# Air_quality.net
KiCad netlist of a schematic drawn in Altium Designer
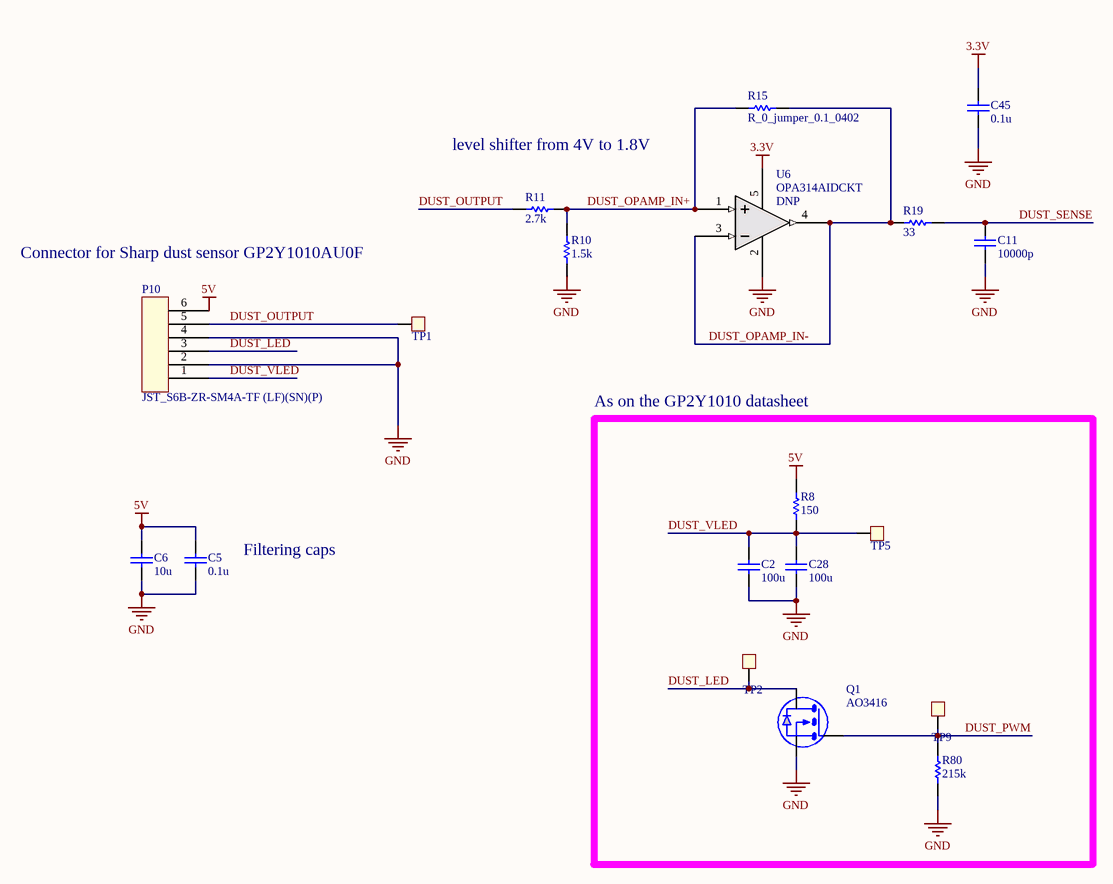
[diagram p0: Air_quality.SchDoc]

(export (version "E")
  (design (tool "Eeschema 10.0.6"))
  (components
    (comp (ref "C2")
      (value "100u")
      (footprint "CAP1206_SENSE_DVT")
      (description "Chip capacitor")
      (fields (field (name "TOLERANCE") "20%") (field (name "VOLTAGE") "10V"))
      (libsource (lib "Morpheus_pill") (part "C_100u_20_10_X5R_1206"))
    )
    (comp (ref "C5")
      (value "0.1u")
      (footprint "CAP0603_SENSE_DVT")
      (description "Chip capacitor")
      (fields (field (name "TOLERANCE") "20%") (field (name "VOLTAGE") "16V"))
      (libsource (lib "Morpheus_pill") (part "C_0.1u_20_16_X7R_0603"))
    )
    (comp (ref "C6")
      (value "10u")
      (footprint "CAP0603_SENSE_DVT")
      (description "Chip capacitor")
      (fields (field (name "TOLERANCE") "10%") (field (name "VOLTAGE") "6.3V"))
      (libsource (lib "Morpheus_pill") (part "C_10u_10_6.3_X5R_0603"))
    )
    (comp (ref "C11")
      (value "10000p")
      (footprint "CAP0402_SENSE_DVT")
      (description "Chip capacitor")
      (fields (field (name "TOLERANCE") "10%") (field (name "VOLTAGE") "50V"))
      (libsource (lib "Morpheus_pill") (part "C_10000p_10_50_X7R_0402"))
    )
    (comp (ref "C28")
      (value "100u")
      (footprint "CAP1206_SENSE_DVT")
      (description "Chip capacitor")
      (fields (field (name "TOLERANCE") "20%") (field (name "VOLTAGE") "10V"))
      (libsource (lib "Morpheus_pill") (part "C_100u_20_10_X5R_1206"))
    )
    (comp (ref "C45")
      (value "0.1u")
      (footprint "CAP0402_SENSE_DVT")
      (description "Chip capacitor")
      (fields (field (name "TOLERANCE") "10%") (field (name "VOLTAGE") "50V"))
      (libsource (lib "Morpheus_pill") (part "C_0.1u_10_50_X7R_0402"))
    )
    (comp (ref "P10")
      (value "JST_S6B-ZR-SM4A-TF (LF)(SN)(P)")
      (footprint "JST_S6B-ZR-SM4A-TF (LF)(SN)(P)")
      (description "6-pin JST connector")
      (libsource (lib "Morpheus_pill") (part "JST_S6B-ZR-SM4A-TF (LF)(SN)(P)"))
    )
    (comp (ref "Q1")
      (value "AO3416")
      (footprint "SOT-23")
      (description "N-channel enhancement mode FET")
      (libsource (lib "Morpheus_pill") (part "AO3416"))
    )
    (comp (ref "R8")
      (value "150")
      (footprint "RES0805_SENSE_DVT")
      (description "Chip Resistor")
      (fields (field (name "TOLERANCE") "5 %") (field (name "POWER") "0.125 W"))
      (libsource (lib "Morpheus_pill") (part "R_150_5_0.125_0805"))
    )
    (comp (ref "R10")
      (value "1.5k")
      (footprint "RES0603_SENSE_DVT")
      (description "Chip Resistor")
      (fields (field (name "TOLERANCE") "1 %") (field (name "POWER") "0.1 W"))
      (libsource (lib "Morpheus_pill") (part "R_1.5k_1_0.1_0603"))
    )
    (comp (ref "R11")
      (value "2.7k")
      (footprint "RES0402_SENSE_DVT")
      (description "RES SMD 2.7K OHM 1% 1/16W 0402")
      (fields (field (name "TOLERANCE") "1 %") (field (name "POWER") "1/16W"))
      (libsource (lib "Morpheus_pill") (part "R_2.7k_1_0.1_0402"))
    )
    (comp (ref "R15")
      (value "R_0_jumper_0.1_0402")
      (footprint "RES0402-SENSE-DVT")
      (description "Chip Resistor")
      (fields (field (name "TOLERANCE") "Jumper") (field (name "POWER") "0.1 W"))
      (libsource (lib "Morpheus_pill") (part "R_0_jumper_0.1_0402"))
    )
    (comp (ref "R19")
      (value "33")
      (footprint "RES0402_SENSE_DVT")
      (description "Chip Resistor")
      (fields (field (name "TOLERANCE") "5 %") (field (name "POWER") "0.1 W"))
      (libsource (lib "Morpheus_pill") (part "R_33_5_0.1_0402"))
    )
    (comp (ref "R80")
      (value "215k")
      (footprint "RES0402_SENSE_DVT")
      (description "Chip Resistor")
      (fields (field (name "TOLERANCE") "1 %") (field (name "POWER") "0.1 W"))
      (libsource (lib "Morpheus_pill") (part "R_215K_1_0.1_0402"))
    )
    (comp (ref "TP1")
      (value "TP")
      (footprint "TP-1.1")
      (description "testpoint")
      (libsource (lib "Morpheus_pill") (part "TP"))
    )
    (comp (ref "TP2")
      (value "TP")
      (footprint "TP-1.1")
      (description "testpoint")
      (libsource (lib "") (part "TP_1"))
    )
    (comp (ref "TP5")
      (value "TP")
      (footprint "TP-1.1")
      (description "testpoint")
      (libsource (lib "Morpheus_pill") (part "TP"))
    )
    (comp (ref "TP9")
      (value "TP")
      (footprint "TP-1.1")
      (description "testpoint")
      (libsource (lib "") (part "TP_1"))
    )
    (comp (ref "U6")
      (value "DNP")
      (footprint "SC-70-5")
      (description "TI single 1.8-5.5V OPAMP")
      (fields (field (name "PN") "OPA314AIDCKT"))
      (libsource (lib "Morpheus_pill") (part "OPA314AIDCKT"))
    )
  )
  (nets
    (net (code "1") (name "/DUST_LED") (class "Default")
      (node (ref "P10") (pin "3") (pintype "passive"))
      (node (ref "Q1") (pin "3") (pinfunction "D_3") (pintype "passive"))
      (node (ref "TP2") (pin "1") (pinfunction "1_1") (pintype "passive"))
    )
    (net (code "2") (name "/DUST_OPAMP_IN+") (class "Default")
      (node (ref "R10") (pin "1") (pinfunction "1_1") (pintype "passive"))
      (node (ref "R11") (pin "2") (pinfunction "2_2") (pintype "passive"))
      (node (ref "R15") (pin "1") (pinfunction "1_1") (pintype "passive"))
      (node (ref "U6") (pin "1") (pinfunction "IN+_1") (pintype "input"))
    )
    (net (code "3") (name "/DUST_OPAMP_IN-") (class "Default")
      (node (ref "R15") (pin "2") (pinfunction "2_2") (pintype "passive"))
      (node (ref "R19") (pin "1") (pinfunction "1_1") (pintype "passive"))
      (node (ref "U6") (pin "3") (pinfunction "IN-_3") (pintype "input"))
      (node (ref "U6") (pin "4") (pinfunction "OUT_4") (pintype "output"))
    )
    (net (code "4") (name "/DUST_OUTPUT") (class "Default")
      (node (ref "P10") (pin "5") (pintype "passive"))
      (node (ref "R11") (pin "1") (pinfunction "1_1") (pintype "passive"))
      (node (ref "TP1") (pin "1") (pinfunction "1_1") (pintype "passive"))
    )
    (net (code "5") (name "/DUST_PWM") (class "Default")
      (node (ref "Q1") (pin "1") (pinfunction "G_1") (pintype "passive"))
      (node (ref "R80") (pin "2") (pinfunction "2_2") (pintype "passive"))
      (node (ref "TP9") (pin "1") (pinfunction "1_1") (pintype "passive"))
    )
    (net (code "6") (name "/DUST_SENSE") (class "Default")
      (node (ref "C11") (pin "2") (pinfunction "2_2") (pintype "passive"))
      (node (ref "R19") (pin "2") (pinfunction "2_2") (pintype "passive"))
    )
    (net (code "7") (name "/DUST_VLED") (class "Default")
      (node (ref "C2") (pin "2") (pinfunction "2_2") (pintype "passive"))
      (node (ref "C28") (pin "2") (pinfunction "2_2") (pintype "passive"))
      (node (ref "P10") (pin "1") (pintype "passive"))
      (node (ref "R8") (pin "1") (pinfunction "1_1") (pintype "passive"))
      (node (ref "TP5") (pin "1") (pinfunction "1_1") (pintype "passive"))
    )
    (net (code "8") (name "3.3V") (class "Default")
      (node (ref "C45") (pin "2") (pinfunction "2_2") (pintype "passive"))
      (node (ref "U6") (pin "5") (pinfunction "V+_5") (pintype "power_in"))
    )
    (net (code "9") (name "5V") (class "Default")
      (node (ref "C5") (pin "2") (pinfunction "2_2") (pintype "passive"))
      (node (ref "C6") (pin "2") (pinfunction "2_2") (pintype "passive"))
      (node (ref "P10") (pin "6") (pintype "passive"))
      (node (ref "R8") (pin "2") (pinfunction "2_2") (pintype "passive"))
    )
    (net (code "10") (name "GND") (class "Default")
      (node (ref "C11") (pin "1") (pinfunction "1_1") (pintype "passive"))
      (node (ref "C2") (pin "1") (pinfunction "1_1") (pintype "passive"))
      (node (ref "C28") (pin "1") (pinfunction "1_1") (pintype "passive"))
      (node (ref "C45") (pin "1") (pinfunction "1_1") (pintype "passive"))
      (node (ref "C5") (pin "1") (pinfunction "1_1") (pintype "passive"))
      (node (ref "C6") (pin "1") (pinfunction "1_1") (pintype "passive"))
      (node (ref "P10") (pin "2") (pintype "passive"))
      (node (ref "P10") (pin "4") (pintype "passive"))
      (node (ref "Q1") (pin "2") (pinfunction "S_2") (pintype "passive"))
      (node (ref "R10") (pin "2") (pinfunction "2_2") (pintype "passive"))
      (node (ref "R80") (pin "1") (pinfunction "1_1") (pintype "passive"))
      (node (ref "U6") (pin "2") (pinfunction "V-_2") (pintype "power_in"))
    )
  )
)
